# LEDBox.net
KiCad netlist of a schematic drawn in EAGLE
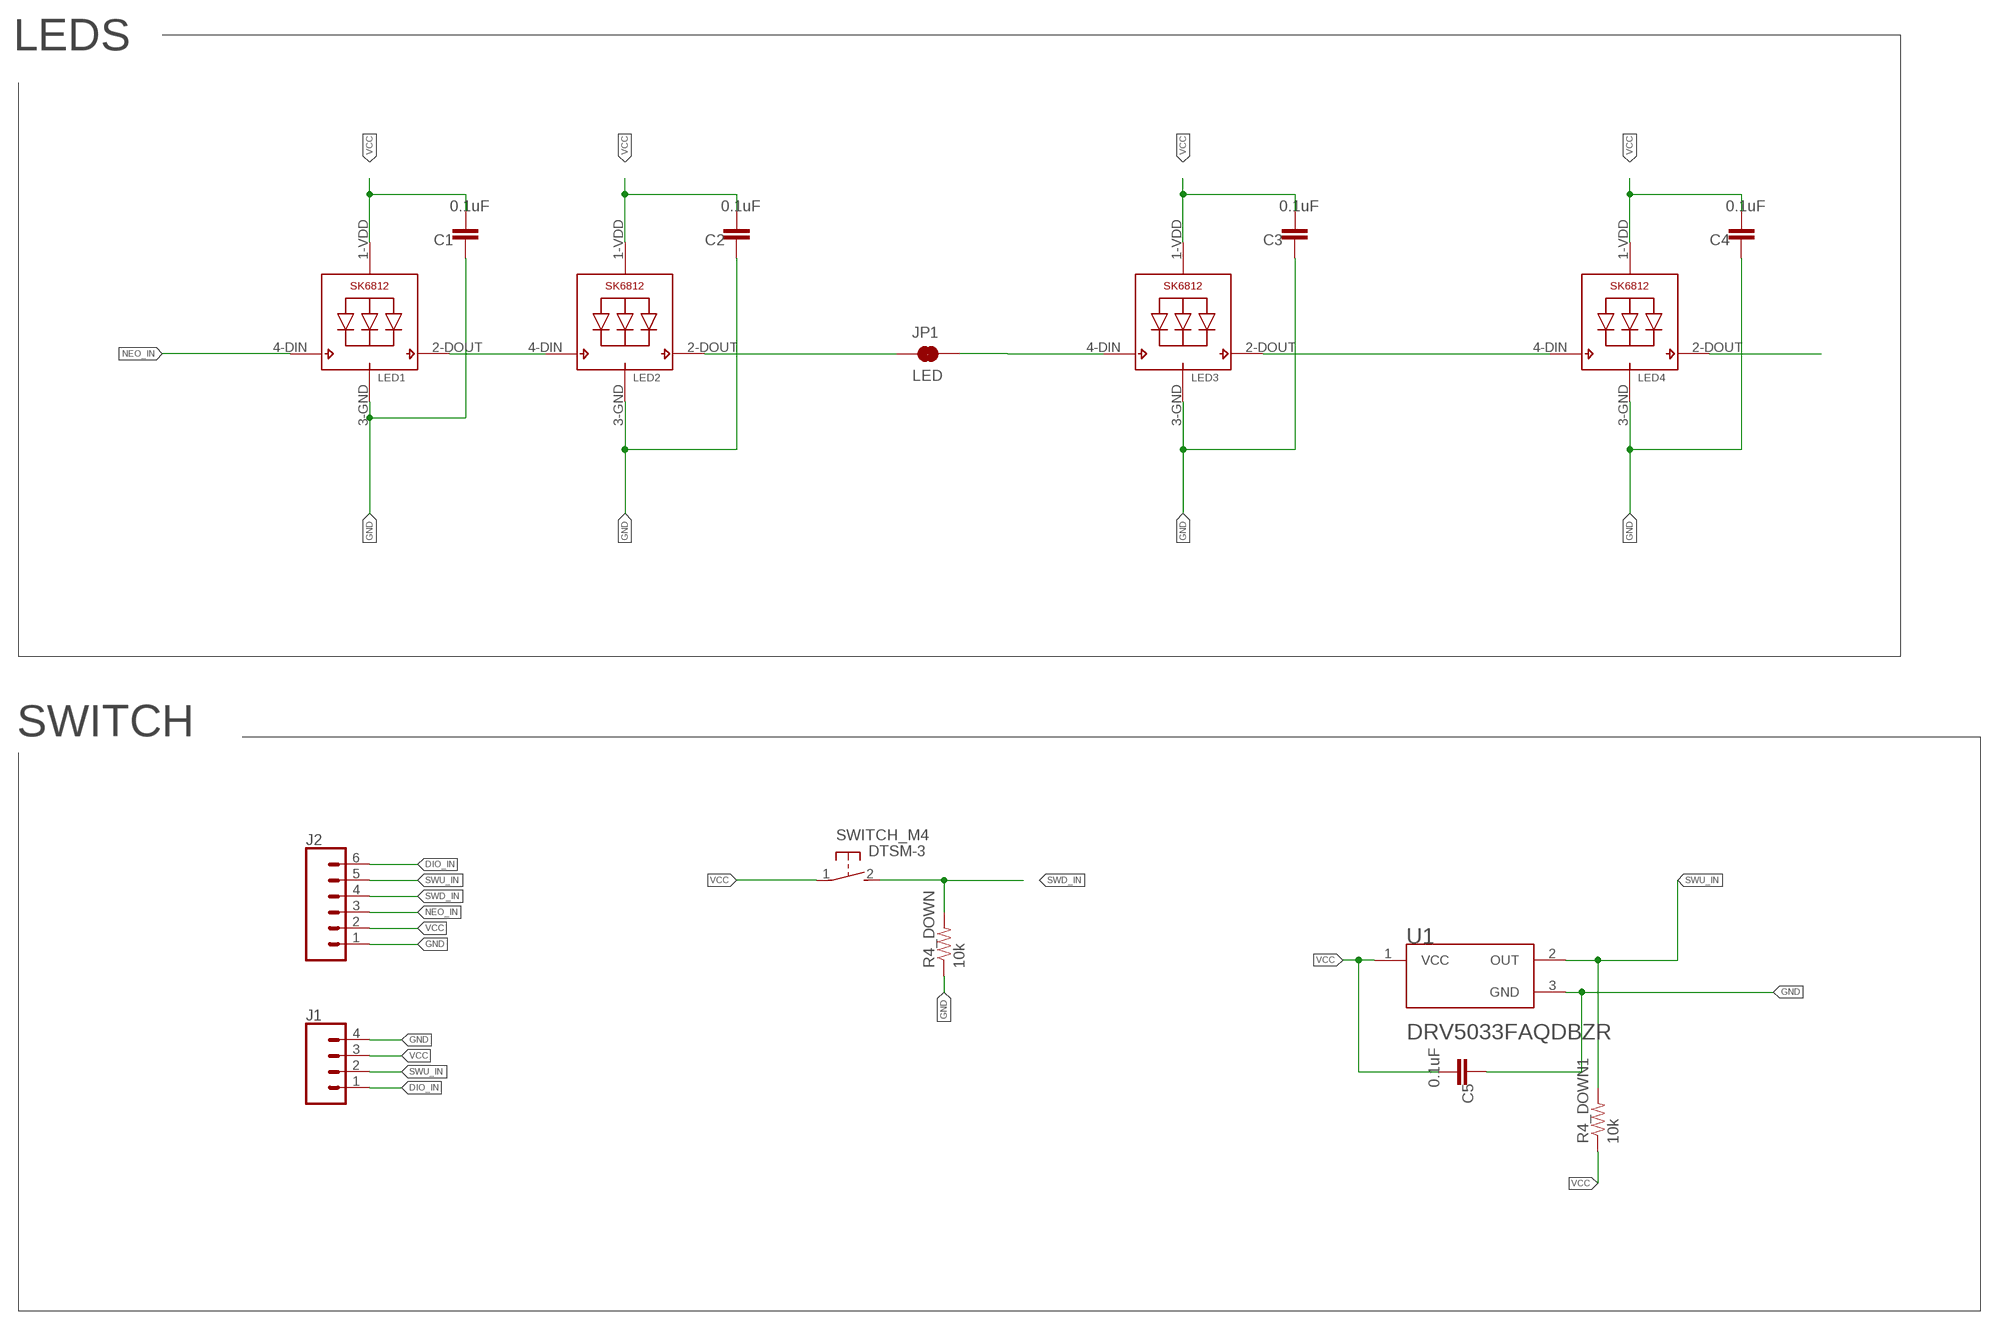
[diagram p0: schematic, sheet 1]

(export (version "E")
  (design (tool "Eeschema 10.0.6"))
  (components
    (comp (ref "C1")
      (value "0.1uF")
      (footprint "eagle-import:0603")
      (libsource (lib "eagle-import") (part "0.1UF-0603-25V-5%"))
    )
    (comp (ref "C2")
      (value "0.1uF")
      (footprint "eagle-import:0603")
      (libsource (lib "eagle-import") (part "0.1UF-0603-25V-5%"))
    )
    (comp (ref "C3")
      (value "0.1uF")
      (footprint "eagle-import:0603")
      (libsource (lib "eagle-import") (part "0.1UF-0603-25V-5%"))
    )
    (comp (ref "C4")
      (value "0.1uF")
      (footprint "eagle-import:0603")
      (libsource (lib "eagle-import") (part "0.1UF-0603-25V-5%"))
    )
    (comp (ref "C5")
      (value "0.1uF")
      (footprint "eagle-import:0603")
      (libsource (lib "eagle-import") (part "0.1UF-0603-25V-5%"))
    )
    (comp (ref "J1")
      (value "CONN_041X04_NO_SILK")
      (footprint "eagle-import:1X04_NO_SILK")
      (libsource (lib "eagle-import") (part "CONN_041X04_NO_SILK"))
    )
    (comp (ref "J2")
      (value "CONN_06SMD-1MM")
      (footprint "eagle-import:1X06-1MM")
      (libsource (lib "eagle-import") (part "CONN_06SMD-1MM"))
    )
    (comp (ref "JP1")
      (value "LED")
      (footprint "eagle-import:SMT-JUMPER_2_NC_TRACE_NO-SILK")
      (libsource (lib "eagle-import") (part "JUMPER-SMT_2_NC_TRACE_NO-SILK"))
    )
    (comp (ref "LED1")
      (value "SK6812_5050W")
      (footprint "eagle-import:LED5050_W")
      (libsource (lib "eagle-import") (part "SK6812_5050W"))
    )
    (comp (ref "LED2")
      (value "SK6812_5050W")
      (footprint "eagle-import:LED5050_W")
      (libsource (lib "eagle-import") (part "SK6812_5050W"))
    )
    (comp (ref "LED3")
      (value "SK6812_5050W")
      (footprint "eagle-import:LED5050_W")
      (libsource (lib "eagle-import") (part "SK6812_5050W"))
    )
    (comp (ref "LED4")
      (value "SK6812_5050W")
      (footprint "eagle-import:LED5050_W")
      (libsource (lib "eagle-import") (part "SK6812_5050W"))
    )
    (comp (ref "R4_DOWN")
      (value "10k")
      (footprint "eagle-import:0603")
      (libsource (lib "eagle-import") (part "10KOHM-0603-1/10W-1%"))
    )
    (comp (ref "R4_DOWN1")
      (value "10k")
      (footprint "eagle-import:0603")
      (libsource (lib "eagle-import") (part "10KOHM-0603-1/10W-1%"))
    )
    (comp (ref "SWITCH_M4")
      (value "DTSM-3")
      (footprint "eagle-import:DTSM-3")
      (libsource (lib "eagle-import") (part "DTSM-3"))
    )
    (comp (ref "U1")
      (value "TEXAS_INSTRUMENTS_DRV5033FAQDBZRTEXAS_INSTRUMENTS_DRV5033FAQDBZR_0_0")
      (footprint "eagle-import:TEXAS_INSTRUMENTS_DRV5033FAQDBZR_0")
      (fields
        (field (name "DIGIKEY_PART_NUMBER") "296-44589-1-ND")
        (field (name "MF") "Texas Instruments")
        (field (name "MOUSER_PART_NUMBER") "595-DRV5033FAQDBZR")
      )
      (libsource (lib "eagle-import") (part "TEXAS_INSTRUMENTS_DRV5033FAQDBZRTEXAS_INSTRUMENTS_DRV5033FAQDBZR_0_0"))
    )
  )
  (nets
    (net (code "1") (name "DIO_IN") (class "Default")
      (node (ref "J1") (pin "1") (pinfunction "1_1") (pintype "passive"))
      (node (ref "J2") (pin "6") (pinfunction "6_6") (pintype "passive"))
    )
    (net (code "2") (name "GND") (class "Default")
      (node (ref "C1") (pin "1") (pinfunction "1_1") (pintype "passive"))
      (node (ref "C2") (pin "1") (pinfunction "1_1") (pintype "passive"))
      (node (ref "C3") (pin "1") (pinfunction "1_1") (pintype "passive"))
      (node (ref "C4") (pin "1") (pinfunction "1_1") (pintype "passive"))
      (node (ref "C5") (pin "1") (pinfunction "1_1") (pintype "passive"))
      (node (ref "J1") (pin "4") (pinfunction "4_4") (pintype "passive"))
      (node (ref "J2") (pin "1") (pinfunction "1_1") (pintype "passive"))
      (node (ref "LED1") (pin "3-GND") (pinfunction "GND_3-GND") (pintype "power_in"))
      (node (ref "LED2") (pin "3-GND") (pinfunction "GND_3-GND") (pintype "power_in"))
      (node (ref "LED3") (pin "3-GND") (pinfunction "GND_3-GND") (pintype "power_in"))
      (node (ref "LED4") (pin "3-GND") (pinfunction "GND_3-GND") (pintype "power_in"))
      (node (ref "R4_DOWN") (pin "1") (pinfunction "1_1") (pintype "passive"))
      (node (ref "U1") (pin "3") (pinfunction "GND_3") (pintype "power_in"))
    )
    (net (code "3") (name "NEO_IN") (class "Default")
      (node (ref "J2") (pin "3") (pinfunction "3_3") (pintype "passive"))
      (node (ref "LED1") (pin "4-DIN") (pinfunction "DI_4-DIN") (pintype "input"))
    )
    (net (code "4") (name "Net-(LED1-DO)") (class "Default")
      (node (ref "LED1") (pin "2-DOUT") (pinfunction "DO_2-DOUT") (pintype "output"))
      (node (ref "LED2") (pin "4-DIN") (pinfunction "DI_4-DIN") (pintype "input"))
    )
    (net (code "5") (name "Net-(LED2-DO)") (class "Default")
      (node (ref "JP1") (pin "1") (pinfunction "1_1") (pintype "passive"))
      (node (ref "LED2") (pin "2-DOUT") (pinfunction "DO_2-DOUT") (pintype "output"))
    )
    (net (code "6") (name "Net-(LED3-DI)") (class "Default")
      (node (ref "JP1") (pin "2") (pinfunction "2_2") (pintype "passive"))
      (node (ref "LED3") (pin "4-DIN") (pinfunction "DI_4-DIN") (pintype "input"))
    )
    (net (code "7") (name "Net-(LED3-DO)") (class "Default")
      (node (ref "LED3") (pin "2-DOUT") (pinfunction "DO_2-DOUT") (pintype "output"))
      (node (ref "LED4") (pin "4-DIN") (pinfunction "DI_4-DIN") (pintype "input"))
    )
    (net (code "8") (name "SWD_IN") (class "Default")
      (node (ref "J2") (pin "4") (pinfunction "4_4") (pintype "passive"))
      (node (ref "R4_DOWN") (pin "2") (pinfunction "2_2") (pintype "passive"))
      (node (ref "SWITCH_M4") (pin "2") (pinfunction "2_2") (pintype "passive"))
    )
    (net (code "9") (name "SWU_IN") (class "Default")
      (node (ref "J1") (pin "2") (pinfunction "2_2") (pintype "passive"))
      (node (ref "J2") (pin "5") (pinfunction "5_5") (pintype "passive"))
      (node (ref "R4_DOWN1") (pin "2") (pinfunction "2_2") (pintype "passive"))
      (node (ref "U1") (pin "2") (pinfunction "OUT_2") (pintype "output"))
    )
    (net (code "10") (name "VCC") (class "Default")
      (node (ref "C1") (pin "2") (pinfunction "2_2") (pintype "passive"))
      (node (ref "C2") (pin "2") (pinfunction "2_2") (pintype "passive"))
      (node (ref "C3") (pin "2") (pinfunction "2_2") (pintype "passive"))
      (node (ref "C4") (pin "2") (pinfunction "2_2") (pintype "passive"))
      (node (ref "C5") (pin "2") (pinfunction "2_2") (pintype "passive"))
      (node (ref "J1") (pin "3") (pinfunction "3_3") (pintype "passive"))
      (node (ref "J2") (pin "2") (pinfunction "2_2") (pintype "passive"))
      (node (ref "LED1") (pin "1-VDD") (pinfunction "VDD_1-VDD") (pintype "power_in"))
      (node (ref "LED2") (pin "1-VDD") (pinfunction "VDD_1-VDD") (pintype "power_in"))
      (node (ref "LED3") (pin "1-VDD") (pinfunction "VDD_1-VDD") (pintype "power_in"))
      (node (ref "LED4") (pin "1-VDD") (pinfunction "VDD_1-VDD") (pintype "power_in"))
      (node (ref "R4_DOWN1") (pin "1") (pinfunction "1_1") (pintype "passive"))
      (node (ref "SWITCH_M4") (pin "1") (pinfunction "1_1") (pintype "passive"))
      (node (ref "U1") (pin "1") (pinfunction "VCC_1") (pintype "power_in"))
    )
    (net (code "11") (name "unconnected-(LED4-DO-Pad2-DOUT)") (class "Default")
      (node (ref "LED4") (pin "2-DOUT") (pinfunction "DO_2-DOUT") (pintype "output"))
    )
  )
)
